# Robotics_lure.net
KiCad netlist of a schematic drawn in EAGLE
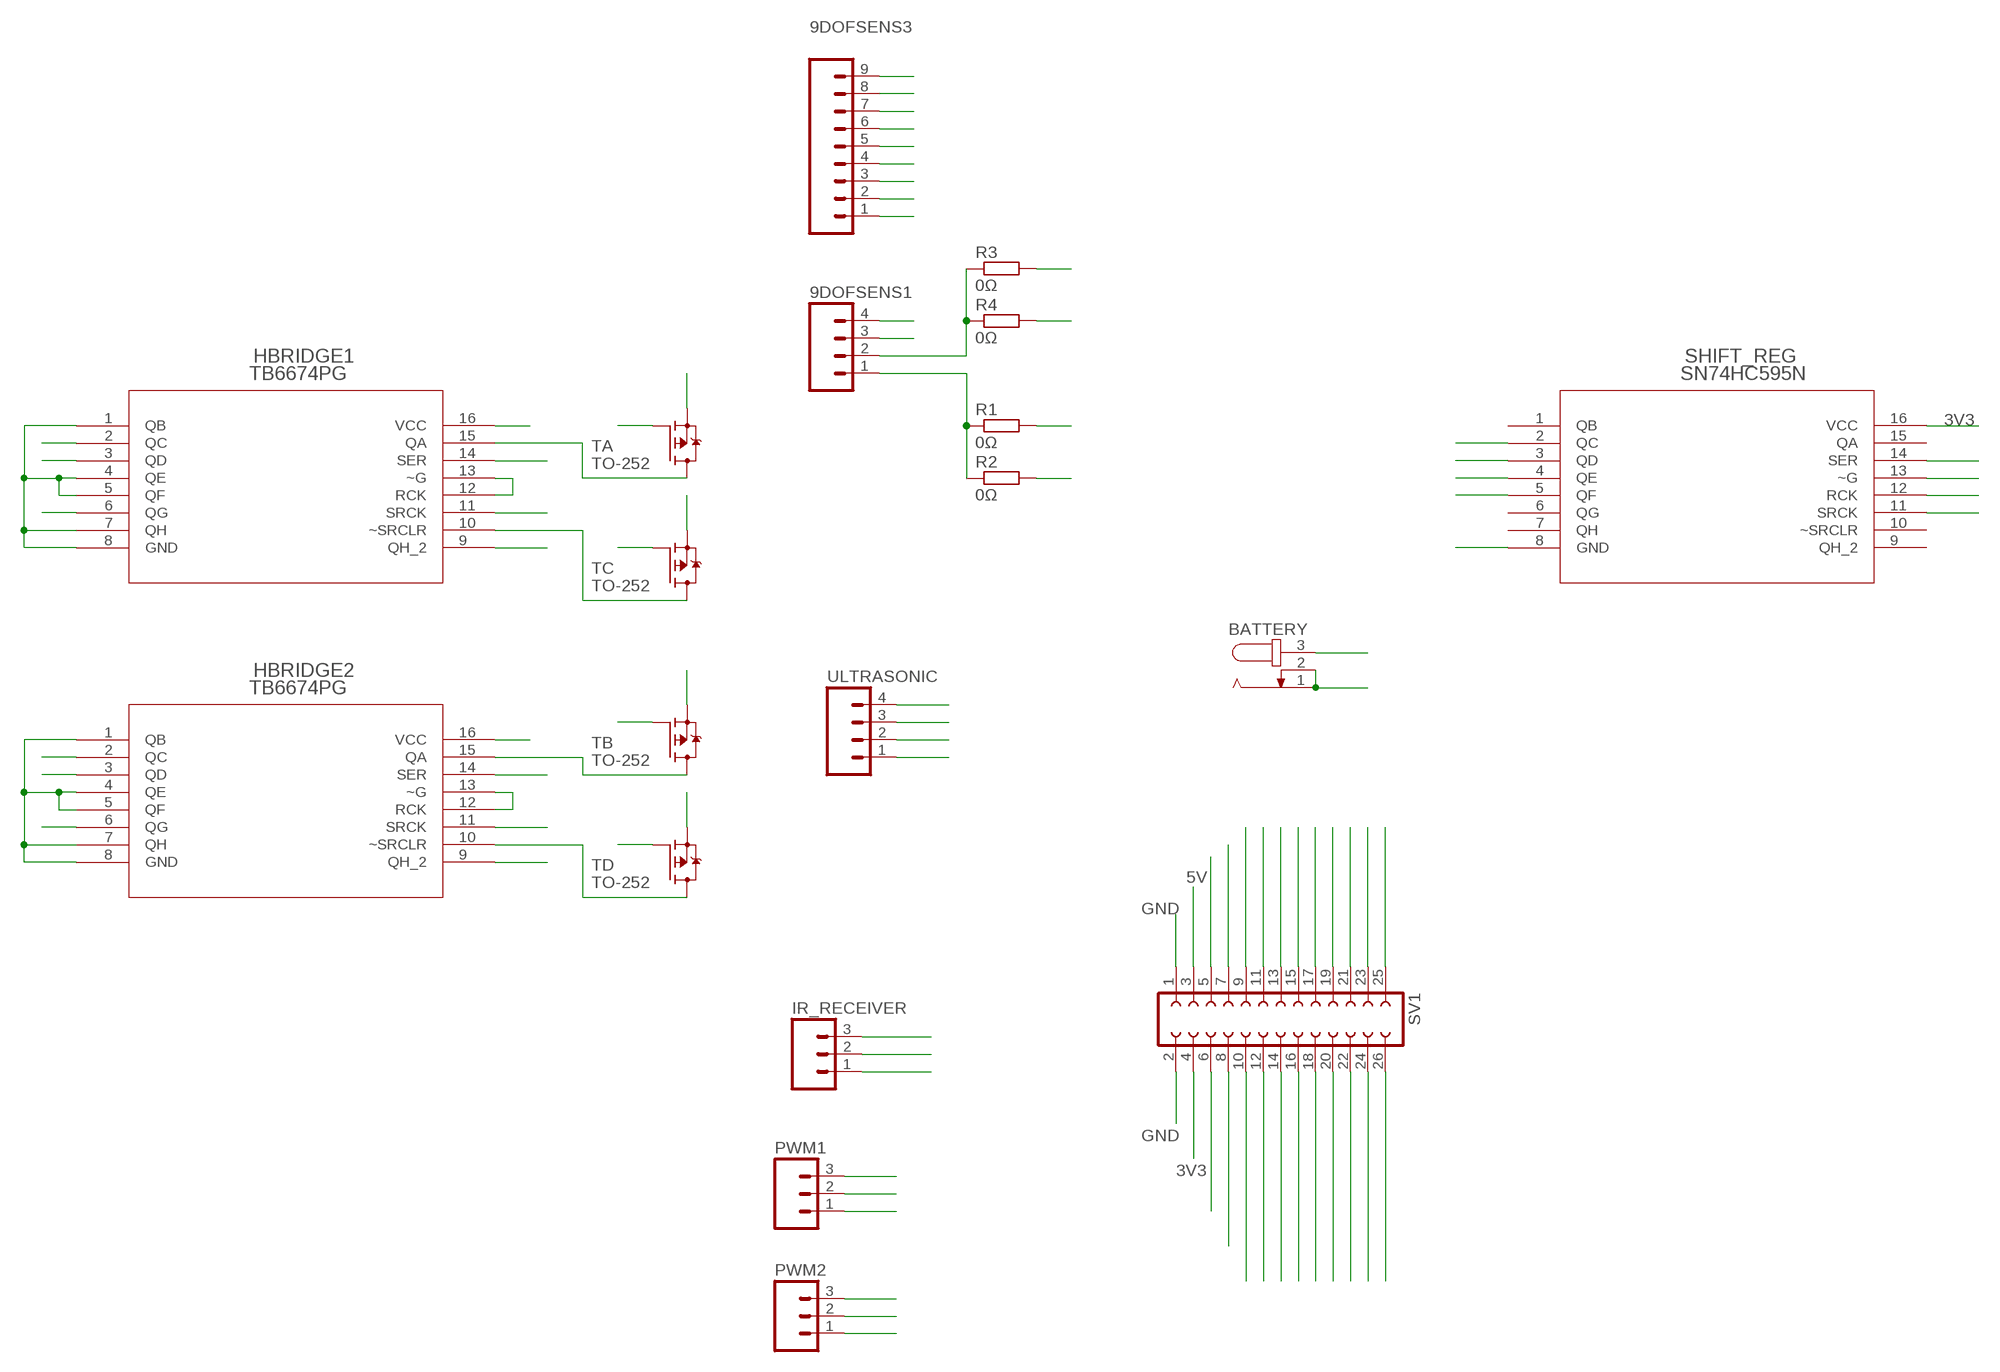
[diagram p0: schematic, sheet 1]

(export (version "E")
  (design (tool "Eeschema 10.0.6"))
  (components
    (comp (ref "9DOFSENS1")
      (value "M04PTH")
      (footprint "eagle-import:1X04")
      (libsource (lib "eagle-import") (part "M04PTH"))
    )
    (comp (ref "9DOFSENS3")
      (value "M09")
      (footprint "eagle-import:1X09")
      (libsource (lib "eagle-import") (part "M09"))
    )
    (comp (ref "BATTERY")
      (value "JACK-PLUG0")
      (footprint "eagle-import:SPC4077")
      (libsource (lib "eagle-import") (part "JACK-PLUG0"))
    )
    (comp (ref "HBRIDGE1")
      (value "TB6674PG")
      (footprint "eagle-import:DIP16_300")
      (fields
        (field (name "DIGIKEYPARTNUMBER") "296-1600-5-ND")
        (field (name "MANUFACTURER_PART_NUMBER") "SN74HC595N")
        (field (name "COPYRIGHT") "Copyright (C) 2015 Accelerated Designs. All rights reserved")
      )
      (libsource (lib "eagle-import") (part "SN74HC595N"))
    )
    (comp (ref "HBRIDGE2")
      (value "TB6674PG")
      (footprint "eagle-import:DIP16_300")
      (fields
        (field (name "DIGIKEYPARTNUMBER") "296-1600-5-ND")
        (field (name "MANUFACTURER_PART_NUMBER") "SN74HC595N")
        (field (name "COPYRIGHT") "Copyright (C) 2015 Accelerated Designs. All rights reserved")
      )
      (libsource (lib "eagle-import") (part "SN74HC595N"))
    )
    (comp (ref "IR_RECEIVER")
      (value "M03PTH")
      (footprint "eagle-import:1X03")
      (libsource (lib "eagle-import") (part "M03PTH"))
    )
    (comp (ref "PWM1")
      (value "M03PTH")
      (footprint "eagle-import:1X03")
      (libsource (lib "eagle-import") (part "M03PTH"))
    )
    (comp (ref "PWM2")
      (value "M03PTH")
      (footprint "eagle-import:1X03")
      (libsource (lib "eagle-import") (part "M03PTH"))
    )
    (comp (ref "R1")
      (value "0Ω")
      (footprint "eagle-import:R1206")
      (libsource (lib "eagle-import") (part "R-EU_R1206"))
    )
    (comp (ref "R2")
      (value "0Ω")
      (footprint "eagle-import:R1206")
      (libsource (lib "eagle-import") (part "R-EU_R1206"))
    )
    (comp (ref "R3")
      (value "0Ω")
      (footprint "eagle-import:R1206")
      (libsource (lib "eagle-import") (part "R-EU_R1206"))
    )
    (comp (ref "R4")
      (value "0Ω")
      (footprint "eagle-import:R1206")
      (libsource (lib "eagle-import") (part "R-EU_R1206"))
    )
    (comp (ref "SHIFT_REG")
      (value "SN74HC595N")
      (footprint "eagle-import:DIP16_300")
      (fields
        (field (name "DIGIKEYPARTNUMBER") "296-1600-5-ND")
        (field (name "COPYRIGHT") "Copyright (C) 2015 Accelerated Designs. All rights reserved")
      )
      (libsource (lib "eagle-import") (part "SN74HC595N"))
    )
    (comp (ref "SV1")
      (value "FE13-2W")
      (footprint "eagle-import:FE13-2W")
      (libsource (lib "eagle-import") (part "FE13-2W"))
    )
    (comp (ref "TA")
      (value "TO-252")
      (footprint "eagle-import:TO252")
      (libsource (lib "eagle-import") (part "SPD30P06PTO252"))
    )
    (comp (ref "TB")
      (value "TO-252")
      (footprint "eagle-import:TO252")
      (libsource (lib "eagle-import") (part "SPD30P06PTO252"))
    )
    (comp (ref "TC")
      (value "TO-252")
      (footprint "eagle-import:TO252")
      (libsource (lib "eagle-import") (part "SPD30P06PTO252"))
    )
    (comp (ref "TD")
      (value "TO-252")
      (footprint "eagle-import:TO252")
      (libsource (lib "eagle-import") (part "SPD30P06PTO252"))
    )
    (comp (ref "ULTRASONIC")
      (value "M04PTH")
      (footprint "eagle-import:1X04")
      (libsource (lib "eagle-import") (part "M04PTH"))
    )
  )
  (nets
    (net (code "1") (name "/3V3") (class "Default")
      (node (ref "9DOFSENS1") (pin "3") (pinfunction "3_3") (pintype "passive"))
      (node (ref "IR_RECEIVER") (pin "1") (pinfunction "1_1") (pintype "passive"))
      (node (ref "SHIFT_REG") (pin "16") (pinfunction "VCC_16") (pintype "passive"))
      (node (ref "SV1") (pin "4") (pinfunction "4_4") (pintype "passive"))
    )
    (net (code "2") (name "/5V") (class "Default")
      (node (ref "HBRIDGE1") (pin "2") (pinfunction "QC_2") (pintype "passive"))
      (node (ref "HBRIDGE2") (pin "2") (pinfunction "QC_2") (pintype "passive"))
      (node (ref "PWM1") (pin "2") (pinfunction "2_2") (pintype "passive"))
      (node (ref "PWM2") (pin "2") (pinfunction "2_2") (pintype "passive"))
      (node (ref "SV1") (pin "3") (pinfunction "3_3") (pintype "passive"))
      (node (ref "ULTRASONIC") (pin "1") (pinfunction "1_1") (pintype "passive"))
    )
    (net (code "3") (name "/14V") (class "Default")
      (node (ref "BATTERY") (pin "3") (pinfunction "3_3") (pintype "passive"))
      (node (ref "HBRIDGE1") (pin "16") (pinfunction "VCC_16") (pintype "passive"))
      (node (ref "HBRIDGE1") (pin "9") (pinfunction "QH_2_9") (pintype "passive"))
      (node (ref "HBRIDGE2") (pin "16") (pinfunction "VCC_16") (pintype "passive"))
      (node (ref "HBRIDGE2") (pin "9") (pinfunction "QH_2_9") (pintype "passive"))
    )
    (net (code "4") (name "/GND") (class "Default")
      (node (ref "9DOFSENS1") (pin "4") (pinfunction "4_4") (pintype "passive"))
      (node (ref "BATTERY") (pin "1") (pinfunction "1_1") (pintype "passive"))
      (node (ref "BATTERY") (pin "2") (pinfunction "2_2") (pintype "passive"))
      (node (ref "HBRIDGE1") (pin "1") (pinfunction "QB_1") (pintype "passive"))
      (node (ref "HBRIDGE1") (pin "12") (pinfunction "RCK_12") (pintype "passive"))
      (node (ref "HBRIDGE1") (pin "13") (pinfunction "~{G}_13") (pintype "passive"))
      (node (ref "HBRIDGE1") (pin "4") (pinfunction "QE_4") (pintype "passive"))
      (node (ref "HBRIDGE1") (pin "5") (pinfunction "QF_5") (pintype "passive"))
      (node (ref "HBRIDGE1") (pin "7") (pinfunction "QH_7") (pintype "passive"))
      (node (ref "HBRIDGE1") (pin "8") (pinfunction "GND_8") (pintype "passive"))
      (node (ref "HBRIDGE2") (pin "1") (pinfunction "QB_1") (pintype "passive"))
      (node (ref "HBRIDGE2") (pin "12") (pinfunction "RCK_12") (pintype "passive"))
      (node (ref "HBRIDGE2") (pin "13") (pinfunction "~{G}_13") (pintype "passive"))
      (node (ref "HBRIDGE2") (pin "4") (pinfunction "QE_4") (pintype "passive"))
      (node (ref "HBRIDGE2") (pin "5") (pinfunction "QF_5") (pintype "passive"))
      (node (ref "HBRIDGE2") (pin "7") (pinfunction "QH_7") (pintype "passive"))
      (node (ref "HBRIDGE2") (pin "8") (pinfunction "GND_8") (pintype "passive"))
      (node (ref "IR_RECEIVER") (pin "2") (pinfunction "2_2") (pintype "passive"))
      (node (ref "PWM1") (pin "1") (pinfunction "1_1") (pintype "passive"))
      (node (ref "PWM2") (pin "1") (pinfunction "1_1") (pintype "passive"))
      (node (ref "SHIFT_REG") (pin "8") (pinfunction "GND_8") (pintype "passive"))
      (node (ref "SV1") (pin "1") (pinfunction "1_1") (pintype "passive"))
      (node (ref "SV1") (pin "2") (pinfunction "2_2") (pintype "passive"))
      (node (ref "ULTRASONIC") (pin "4") (pinfunction "4_4") (pintype "passive"))
    )
    (net (code "5") (name "/GPIO_I2C_SCL_(I2C#5)") (class "Default")
      (node (ref "R1") (pin "2") (pinfunction "2_2") (pintype "passive"))
      (node (ref "SV1") (pin "13") (pinfunction "13_13") (pintype "passive"))
    )
    (net (code "6") (name "/GPIO_I2C_SDA_(I2C_#5)") (class "Default")
      (node (ref "R3") (pin "2") (pinfunction "2_2") (pintype "passive"))
      (node (ref "SV1") (pin "15") (pinfunction "15_15") (pintype "passive"))
    )
    (net (code "7") (name "/GPIO_I2S_CLK") (class "Default")
      (node (ref "9DOFSENS3") (pin "1") (pinfunction "1_1") (pintype "passive"))
      (node (ref "SV1") (pin "14") (pinfunction "14_14") (pintype "passive"))
    )
    (net (code "8") (name "/GPIO_I2S_DI") (class "Default")
      (node (ref "9DOFSENS3") (pin "3") (pinfunction "3_3") (pintype "passive"))
      (node (ref "9DOFSENS3") (pin "8") (pinfunction "8_8") (pintype "passive"))
      (node (ref "SV1") (pin "20") (pinfunction "20_20") (pintype "passive"))
    )
    (net (code "9") (name "/GPIO_I2S_DO") (class "Default")
      (node (ref "9DOFSENS3") (pin "5") (pinfunction "5_5") (pintype "passive"))
      (node (ref "SV1") (pin "18") (pinfunction "18_18") (pintype "passive"))
    )
    (net (code "10") (name "/GPIO_PWM0") (class "Default")
      (node (ref "PWM1") (pin "3") (pinfunction "3_3") (pintype "passive"))
      (node (ref "SV1") (pin "22") (pinfunction "22_22") (pintype "passive"))
    )
    (net (code "11") (name "/GPIO_PWM1") (class "Default")
      (node (ref "PWM2") (pin "3") (pinfunction "3_3") (pintype "passive"))
      (node (ref "SV1") (pin "24") (pinfunction "24_24") (pintype "passive"))
    )
    (net (code "12") (name "/GPIO_S5_0") (class "Default")
      (node (ref "SHIFT_REG") (pin "14") (pinfunction "SER_14") (pintype "passive"))
      (node (ref "SV1") (pin "21") (pinfunction "21_21") (pintype "passive"))
    )
    (net (code "13") (name "/GPIO_S5_1") (class "Default")
      (node (ref "SHIFT_REG") (pin "13") (pinfunction "~{G}_13") (pintype "passive"))
      (node (ref "SV1") (pin "23") (pinfunction "23_23") (pintype "passive"))
    )
    (net (code "14") (name "/GPIO_S5_2") (class "Default")
      (node (ref "SHIFT_REG") (pin "12") (pinfunction "RCK_12") (pintype "passive"))
      (node (ref "SV1") (pin "25") (pinfunction "25_25") (pintype "passive"))
    )
    (net (code "15") (name "/GPIO_SPI_CLK") (class "Default")
      (node (ref "R4") (pin "2") (pinfunction "2_2") (pintype "passive"))
      (node (ref "SV1") (pin "11") (pinfunction "11_11") (pintype "passive"))
    )
    (net (code "16") (name "/GPIO_SPI_CS#") (class "Default")
      (node (ref "SV1") (pin "5") (pinfunction "5_5") (pintype "passive"))
      (node (ref "ULTRASONIC") (pin "2") (pinfunction "2_2") (pintype "passive"))
    )
    (net (code "17") (name "/GPIO_SPI_MISO") (class "Default")
      (node (ref "9DOFSENS3") (pin "9") (pinfunction "9_9") (pintype "passive"))
      (node (ref "SV1") (pin "7") (pinfunction "7_7") (pintype "passive"))
    )
    (net (code "18") (name "/GPIO_SPI_MOSI") (class "Default")
      (node (ref "R2") (pin "2") (pinfunction "2_2") (pintype "passive"))
      (node (ref "SV1") (pin "9") (pinfunction "9_9") (pintype "passive"))
    )
    (net (code "19") (name "/GPIO_UART1_CTS") (class "Default")
      (node (ref "9DOFSENS3") (pin "7") (pinfunction "7_7") (pintype "passive"))
      (node (ref "SV1") (pin "10") (pinfunction "10_10") (pintype "passive"))
    )
    (net (code "20") (name "/GPIO_UART1_RTS") (class "Default")
      (node (ref "9DOFSENS3") (pin "6") (pinfunction "6_6") (pintype "passive"))
      (node (ref "SV1") (pin "12") (pinfunction "12_12") (pintype "passive"))
    )
    (net (code "21") (name "/GPIO_UART1_RXD") (class "Default")
      (node (ref "IR_RECEIVER") (pin "3") (pinfunction "3_3") (pintype "passive"))
      (node (ref "SV1") (pin "8") (pinfunction "8_8") (pintype "passive"))
    )
    (net (code "22") (name "/GPIO_UART1_TXD") (class "Default")
      (node (ref "SV1") (pin "6") (pinfunction "6_6") (pintype "passive"))
      (node (ref "ULTRASONIC") (pin "3") (pinfunction "3_3") (pintype "passive"))
    )
    (net (code "23") (name "/GPIO_UART2_RXD") (class "Default")
      (node (ref "9DOFSENS3") (pin "2") (pinfunction "2_2") (pintype "passive"))
      (node (ref "SV1") (pin "19") (pinfunction "19_19") (pintype "passive"))
    )
    (net (code "24") (name "/GPIO_UART2_TXD") (class "Default")
      (node (ref "9DOFSENS3") (pin "4") (pinfunction "4_4") (pintype "passive"))
      (node (ref "SV1") (pin "17") (pinfunction "17_17") (pintype "passive"))
    )
    (net (code "25") (name "/I2SMCLK_GPIO") (class "Default")
      (node (ref "SHIFT_REG") (pin "11") (pinfunction "SRCK_11") (pintype "passive"))
      (node (ref "SV1") (pin "26") (pinfunction "26_26") (pintype "passive"))
    )
    (net (code "26") (name "/MOTACTRL") (class "Default")
      (node (ref "HBRIDGE1") (pin "3") (pinfunction "QD_3") (pintype "passive"))
      (node (ref "SHIFT_REG") (pin "2") (pinfunction "QC_2") (pintype "passive"))
      (node (ref "TA") (pin "1") (pinfunction "G_1") (pintype "passive"))
    )
    (net (code "27") (name "/MOTBCTRL") (class "Default")
      (node (ref "HBRIDGE2") (pin "3") (pinfunction "QD_3") (pintype "passive"))
      (node (ref "SHIFT_REG") (pin "3") (pinfunction "QD_3") (pintype "passive"))
      (node (ref "TB") (pin "1") (pinfunction "G_1") (pintype "passive"))
    )
    (net (code "28") (name "/MOTCCTRL") (class "Default")
      (node (ref "HBRIDGE1") (pin "6") (pinfunction "QG_6") (pintype "passive"))
      (node (ref "SHIFT_REG") (pin "4") (pinfunction "QE_4") (pintype "passive"))
      (node (ref "TC") (pin "1") (pinfunction "G_1") (pintype "passive"))
    )
    (net (code "29") (name "/MOTDCTRL") (class "Default")
      (node (ref "HBRIDGE2") (pin "6") (pinfunction "QG_6") (pintype "passive"))
      (node (ref "SHIFT_REG") (pin "5") (pinfunction "QF_5") (pintype "passive"))
      (node (ref "TD") (pin "1") (pinfunction "G_1") (pintype "passive"))
    )
    (net (code "30") (name "Net-(9DOFSENS1-Pad1)") (class "Default")
      (node (ref "9DOFSENS1") (pin "1") (pinfunction "1_1") (pintype "passive"))
      (node (ref "R1") (pin "1") (pinfunction "1_1") (pintype "passive"))
      (node (ref "R2") (pin "1") (pinfunction "1_1") (pintype "passive"))
    )
    (net (code "31") (name "Net-(9DOFSENS1-Pad2)") (class "Default")
      (node (ref "9DOFSENS1") (pin "2") (pinfunction "2_2") (pintype "passive"))
      (node (ref "R3") (pin "1") (pinfunction "1_1") (pintype "passive"))
      (node (ref "R4") (pin "1") (pinfunction "1_1") (pintype "passive"))
    )
    (net (code "32") (name "Net-(HBRIDGE1-QA)") (class "Default")
      (node (ref "HBRIDGE1") (pin "15") (pinfunction "QA_15") (pintype "passive"))
      (node (ref "TA") (pin "3") (pinfunction "D_3") (pintype "passive"))
    )
    (net (code "33") (name "Net-(HBRIDGE1-~{SRCLR})") (class "Default")
      (node (ref "HBRIDGE1") (pin "10") (pinfunction "~{SRCLR}_10") (pintype "passive"))
      (node (ref "TC") (pin "3") (pinfunction "D_3") (pintype "passive"))
    )
    (net (code "34") (name "Net-(HBRIDGE2-QA)") (class "Default")
      (node (ref "HBRIDGE2") (pin "15") (pinfunction "QA_15") (pintype "passive"))
      (node (ref "TB") (pin "3") (pinfunction "D_3") (pintype "passive"))
    )
    (net (code "35") (name "Net-(HBRIDGE2-~{SRCLR})") (class "Default")
      (node (ref "HBRIDGE2") (pin "10") (pinfunction "~{SRCLR}_10") (pintype "passive"))
      (node (ref "TD") (pin "3") (pinfunction "D_3") (pintype "passive"))
    )
    (net (code "36") (name "unconnected-(HBRIDGE1-SER-Pad14)") (class "Default")
      (node (ref "HBRIDGE1") (pin "14") (pinfunction "SER_14") (pintype "passive"))
    )
    (net (code "37") (name "unconnected-(HBRIDGE1-SRCK-Pad11)") (class "Default")
      (node (ref "HBRIDGE1") (pin "11") (pinfunction "SRCK_11") (pintype "passive"))
    )
    (net (code "38") (name "unconnected-(HBRIDGE2-SER-Pad14)") (class "Default")
      (node (ref "HBRIDGE2") (pin "14") (pinfunction "SER_14") (pintype "passive"))
    )
    (net (code "39") (name "unconnected-(HBRIDGE2-SRCK-Pad11)") (class "Default")
      (node (ref "HBRIDGE2") (pin "11") (pinfunction "SRCK_11") (pintype "passive"))
    )
    (net (code "40") (name "unconnected-(SHIFT_REG-QA-Pad15)") (class "Default")
      (node (ref "SHIFT_REG") (pin "15") (pinfunction "QA_15") (pintype "passive"))
    )
    (net (code "41") (name "unconnected-(SHIFT_REG-QB-Pad1)") (class "Default")
      (node (ref "SHIFT_REG") (pin "1") (pinfunction "QB_1") (pintype "passive"))
    )
    (net (code "42") (name "unconnected-(SHIFT_REG-QG-Pad6)") (class "Default")
      (node (ref "SHIFT_REG") (pin "6") (pinfunction "QG_6") (pintype "passive"))
    )
    (net (code "43") (name "unconnected-(SHIFT_REG-QH-Pad7)") (class "Default")
      (node (ref "SHIFT_REG") (pin "7") (pinfunction "QH_7") (pintype "passive"))
    )
    (net (code "44") (name "unconnected-(SHIFT_REG-QH_2-Pad9)") (class "Default")
      (node (ref "SHIFT_REG") (pin "9") (pinfunction "QH_2_9") (pintype "passive"))
    )
    (net (code "45") (name "unconnected-(SHIFT_REG-~{SRCLR}-Pad10)") (class "Default")
      (node (ref "SHIFT_REG") (pin "10") (pinfunction "~{SRCLR}_10") (pintype "passive"))
    )
    (net (code "46") (name "unconnected-(SV1-Pad16)") (class "Default")
      (node (ref "SV1") (pin "16") (pinfunction "16_16") (pintype "passive"))
    )
    (net (code "47") (name "unconnected-(TA-S-Pad2)") (class "Default")
      (node (ref "TA") (pin "2") (pinfunction "S_2") (pintype "passive"))
    )
    (net (code "48") (name "unconnected-(TB-S-Pad2)") (class "Default")
      (node (ref "TB") (pin "2") (pinfunction "S_2") (pintype "passive"))
    )
    (net (code "49") (name "unconnected-(TC-S-Pad2)") (class "Default")
      (node (ref "TC") (pin "2") (pinfunction "S_2") (pintype "passive"))
    )
    (net (code "50") (name "unconnected-(TD-S-Pad2)") (class "Default")
      (node (ref "TD") (pin "2") (pinfunction "S_2") (pintype "passive"))
    )
  )
)
